# Second_try.net
KiCad netlist of a schematic drawn in EAGLE
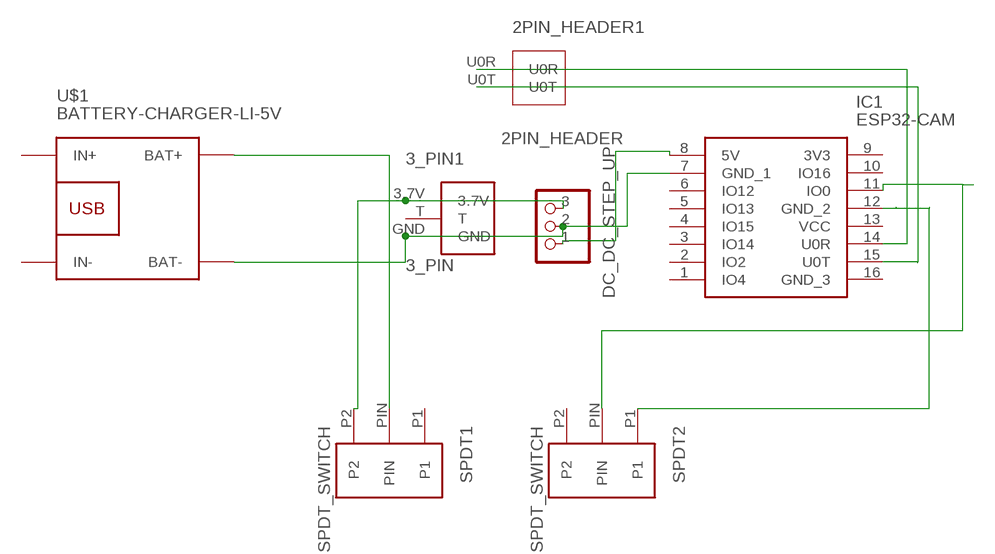
[diagram p0: schematic, sheet 1]

(export (version "E")
  (design (tool "Eeschema 10.0.6"))
  (components
    (comp (ref "2PIN_HEADER1")
      (value "2PIN_HEADER")
      (footprint "eagle-import:2PIN_HEADER")
      (libsource (lib "eagle-import") (part "2PIN_HEADER"))
    )
    (comp (ref "3_PIN1")
      (value "3_PIN")
      (footprint "eagle-import:3_PIN")
      (libsource (lib "eagle-import") (part "3_PIN"))
    )
    (comp (ref "DC_DC_STEP_UP")
      (value "PINHD-1X3")
      (footprint "eagle-import:1X03")
      (libsource (lib "eagle-import") (part "PINHD-1X3"))
    )
    (comp (ref "IC1")
      (value "ESP32-CAM")
      (footprint "eagle-import:ESP32CAM")
      (libsource (lib "eagle-import") (part "ESP32-CAM"))
    )
    (comp (ref "SPDT1")
      (value "SPDT_SWITCH")
      (footprint "eagle-import:SPDT_SWITCH")
      (libsource (lib "eagle-import") (part "SPDT_SWITCH"))
    )
    (comp (ref "SPDT2")
      (value "SPDT_SWITCH")
      (footprint "eagle-import:SPDT_SWITCH")
      (libsource (lib "eagle-import") (part "SPDT_SWITCH"))
    )
    (comp (ref "U$1")
      (value "BATTERY-CHARGER-LI-5V")
      (footprint "eagle-import:BATTERY-CHARGER-LI-5V")
      (libsource (lib "eagle-import") (part "BATTERY-CHARGER-LI-5V"))
    )
  )
  (nets
    (net (code "1") (name "Net-(3_PIN1-Pad3.7V)") (class "Default")
      (node (ref "3_PIN1") (pin "3.7V") (pinfunction "3.7V_3.7V") (pintype "bidirectional"))
      (node (ref "DC_DC_STEP_UP") (pin "3") (pinfunction "3_3") (pintype "passive"))
      (node (ref "SPDT1") (pin "P2") (pinfunction "P2_P2") (pintype "bidirectional"))
    )
    (net (code "2") (name "Net-(IC1-5V)") (class "Default")
      (node (ref "DC_DC_STEP_UP") (pin "1") (pinfunction "1_1") (pintype "passive"))
      (node (ref "IC1") (pin "8") (pinfunction "5V_8") (pintype "bidirectional"))
    )
    (net (code "3") (name "Net-(IC1-GND_1)") (class "Default")
      (node (ref "3_PIN1") (pin "GND") (pinfunction "GND_GND") (pintype "bidirectional"))
      (node (ref "DC_DC_STEP_UP") (pin "2") (pinfunction "2_2") (pintype "passive"))
      (node (ref "IC1") (pin "7") (pinfunction "GND_1_7") (pintype "bidirectional"))
      (node (ref "U$1") (pin "BAT-") (pinfunction "BAT-_BAT-") (pintype "bidirectional"))
    )
    (net (code "4") (name "Net-(IC1-GND_2)") (class "Default")
      (node (ref "IC1") (pin "12") (pinfunction "GND_2_12") (pintype "bidirectional"))
      (node (ref "SPDT2") (pin "P1") (pinfunction "P1_P1") (pintype "bidirectional"))
    )
    (net (code "5") (name "Net-(IC1-IO0)") (class "Default")
      (node (ref "IC1") (pin "11") (pinfunction "IO0_11") (pintype "bidirectional"))
      (node (ref "SPDT2") (pin "PIN") (pinfunction "PIN_PIN") (pintype "bidirectional"))
    )
    (net (code "6") (name "Net-(IC1-U0R)") (class "Default")
      (node (ref "2PIN_HEADER1") (pin "U0R") (pinfunction "U0R_U0R") (pintype "bidirectional"))
      (node (ref "IC1") (pin "14") (pinfunction "U0R_14") (pintype "bidirectional"))
    )
    (net (code "7") (name "Net-(IC1-U0T)") (class "Default")
      (node (ref "2PIN_HEADER1") (pin "U0T") (pinfunction "U0T_U0T") (pintype "bidirectional"))
      (node (ref "IC1") (pin "15") (pinfunction "U0T_15") (pintype "bidirectional"))
    )
    (net (code "8") (name "Net-(SPDT1-PadPIN)") (class "Default")
      (node (ref "SPDT1") (pin "PIN") (pinfunction "PIN_PIN") (pintype "bidirectional"))
      (node (ref "U$1") (pin "BAT+") (pinfunction "BAT+_BAT+") (pintype "bidirectional"))
    )
    (net (code "9") (name "unconnected-(3_PIN1-PadT)") (class "Default")
      (node (ref "3_PIN1") (pin "T") (pinfunction "T_T") (pintype "bidirectional"))
    )
    (net (code "10") (name "unconnected-(IC1-3V3-Pad9)") (class "Default")
      (node (ref "IC1") (pin "9") (pinfunction "3V3_9") (pintype "bidirectional"))
    )
    (net (code "11") (name "unconnected-(IC1-GND_3-Pad16)") (class "Default")
      (node (ref "IC1") (pin "16") (pinfunction "GND_3_16") (pintype "bidirectional"))
    )
    (net (code "12") (name "unconnected-(IC1-IO2-Pad2)") (class "Default")
      (node (ref "IC1") (pin "2") (pinfunction "IO2_2") (pintype "bidirectional"))
    )
    (net (code "13") (name "unconnected-(IC1-IO4-Pad1)") (class "Default")
      (node (ref "IC1") (pin "1") (pinfunction "IO4_1") (pintype "bidirectional"))
    )
    (net (code "14") (name "unconnected-(IC1-IO12-Pad6)") (class "Default")
      (node (ref "IC1") (pin "6") (pinfunction "IO12_6") (pintype "bidirectional"))
    )
    (net (code "15") (name "unconnected-(IC1-IO13-Pad5)") (class "Default")
      (node (ref "IC1") (pin "5") (pinfunction "IO13_5") (pintype "bidirectional"))
    )
    (net (code "16") (name "unconnected-(IC1-IO14-Pad3)") (class "Default")
      (node (ref "IC1") (pin "3") (pinfunction "IO14_3") (pintype "bidirectional"))
    )
    (net (code "17") (name "unconnected-(IC1-IO15-Pad4)") (class "Default")
      (node (ref "IC1") (pin "4") (pinfunction "IO15_4") (pintype "bidirectional"))
    )
    (net (code "18") (name "unconnected-(IC1-IO16-Pad10)") (class "Default")
      (node (ref "IC1") (pin "10") (pinfunction "IO16_10") (pintype "bidirectional"))
    )
    (net (code "19") (name "unconnected-(IC1-VCC-Pad13)") (class "Default")
      (node (ref "IC1") (pin "13") (pinfunction "VCC_13") (pintype "bidirectional"))
    )
    (net (code "20") (name "unconnected-(SPDT1-PadP1)") (class "Default")
      (node (ref "SPDT1") (pin "P1") (pinfunction "P1_P1") (pintype "bidirectional"))
    )
    (net (code "21") (name "unconnected-(SPDT2-PadP2)") (class "Default")
      (node (ref "SPDT2") (pin "P2") (pinfunction "P2_P2") (pintype "bidirectional"))
    )
    (net (code "22") (name "unconnected-(U$1-PadIN+)") (class "Default")
      (node (ref "U$1") (pin "IN+") (pinfunction "IN+_IN+") (pintype "bidirectional"))
    )
    (net (code "23") (name "unconnected-(U$1-PadIN-)") (class "Default")
      (node (ref "U$1") (pin "IN-") (pinfunction "IN-_IN-") (pintype "bidirectional"))
    )
  )
)
